# RAM_FLASH.net
KiCad netlist of a schematic drawn in Altium Designer
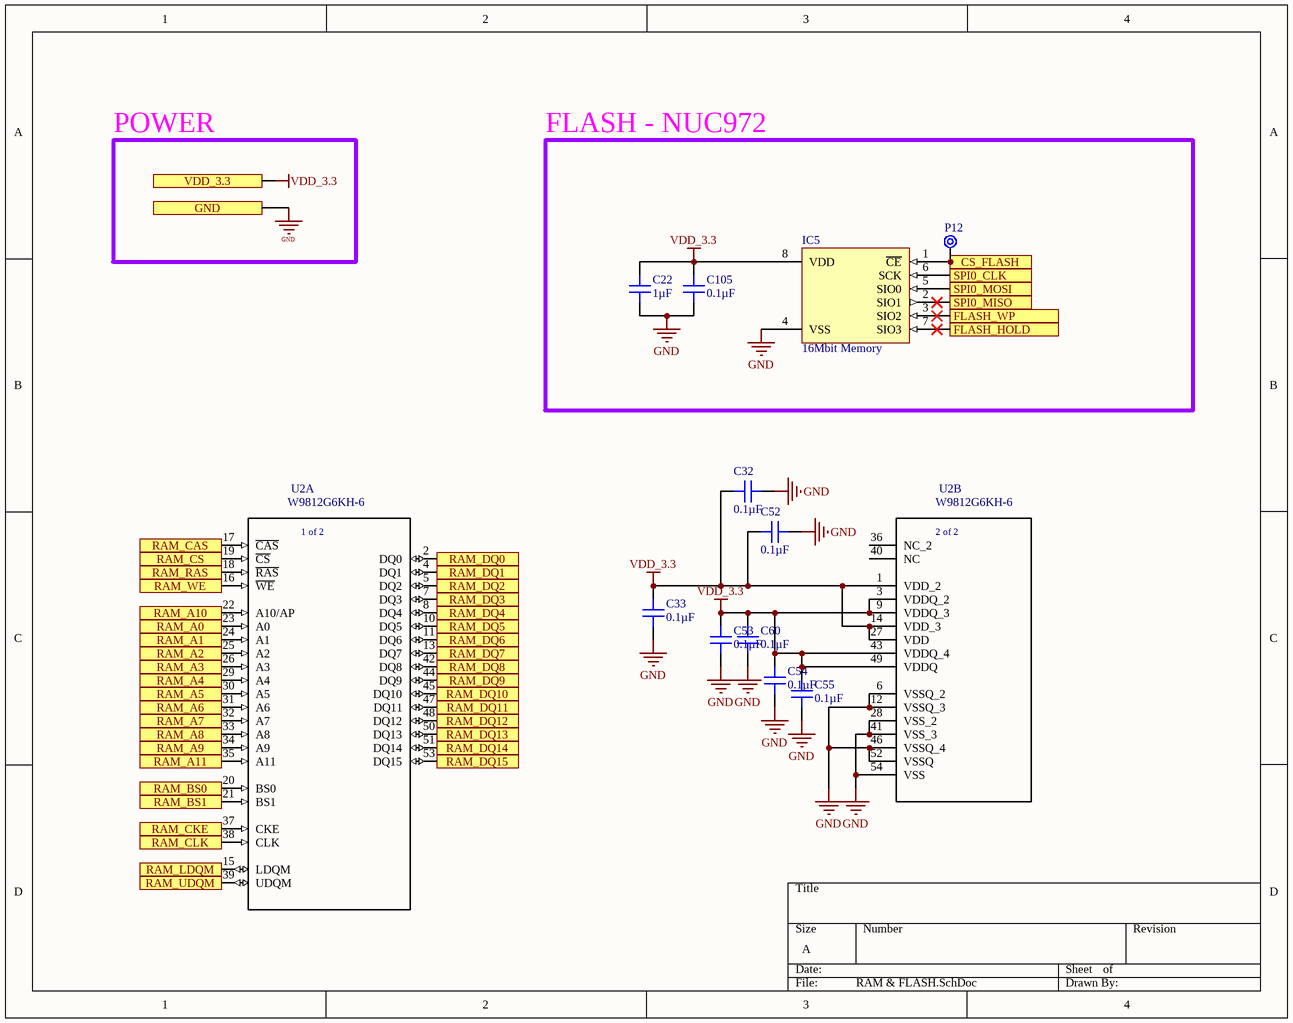
[diagram p0: RAM & FLASH.SchDoc]

(export (version "E")
  (design (tool "Eeschema 10.0.6"))
  (components
    (comp (ref "C22")
      (value "1µF")
      (footprint "CAP 0603_1608")
      (description "CAP CER 1UF 10V X7R 0603")
      (fields (field (name "MANUFACTURER") "KEMET") (field (name "VOLTAGE") "10V"))
      (libsource (lib "MVVVMAltiumDatabase") (part "Capacitor"))
    )
    (comp (ref "C32")
      (value "0.1µF")
      (footprint "CAP 0603_1608 RF")
      (description "CAP CER 0.1UF 16V X7R 0603")
      (fields (field (name "MANUFACTURER") "KEMET") (field (name "VOLTAGE") "16V"))
      (libsource (lib "MVVVMAltiumDatabase") (part "Capacitor"))
    )
    (comp (ref "C33")
      (value "0.1µF")
      (footprint "CAP 0603_1608 RF")
      (description "CAP CER 0.1UF 16V X7R 0603")
      (fields (field (name "MANUFACTURER") "KEMET") (field (name "VOLTAGE") "16V"))
      (libsource (lib "MVVVMAltiumDatabase") (part "Capacitor"))
    )
    (comp (ref "C52")
      (value "0.1µF")
      (footprint "CAP 0603_1608 RF")
      (description "CAP CER 0.1UF 16V X7R 0603")
      (fields (field (name "MANUFACTURER") "KEMET") (field (name "VOLTAGE") "16V"))
      (libsource (lib "MVVVMAltiumDatabase") (part "Capacitor"))
    )
    (comp (ref "C53")
      (value "0.1µF")
      (footprint "CAP 0603_1608 RF")
      (description "CAP CER 0.1UF 16V X7R 0603")
      (fields (field (name "MANUFACTURER") "KEMET") (field (name "VOLTAGE") "16V"))
      (libsource (lib "MVVVMAltiumDatabase") (part "Capacitor"))
    )
    (comp (ref "C54")
      (value "0.1µF")
      (footprint "CAP 0603_1608 RF")
      (description "CAP CER 0.1UF 16V X7R 0603")
      (fields (field (name "MANUFACTURER") "KEMET") (field (name "VOLTAGE") "16V"))
      (libsource (lib "MVVVMAltiumDatabase") (part "Capacitor"))
    )
    (comp (ref "C55")
      (value "0.1µF")
      (footprint "CAP 0603_1608 RF")
      (description "CAP CER 0.1UF 16V X7R 0603")
      (fields (field (name "MANUFACTURER") "KEMET") (field (name "VOLTAGE") "16V"))
      (libsource (lib "MVVVMAltiumDatabase") (part "Capacitor"))
    )
    (comp (ref "C60")
      (value "0.1µF")
      (footprint "CAP 0603_1608 RF")
      (description "CAP CER 0.1UF 16V X7R 0603")
      (fields (field (name "MANUFACTURER") "KEMET") (field (name "VOLTAGE") "16V"))
      (libsource (lib "MVVVMAltiumDatabase") (part "Capacitor"))
    )
    (comp (ref "C105")
      (value "0.1µF")
      (footprint "CAP 0603_1608 RF")
      (description "CAP CER 0.1UF 16V X7R 0603")
      (fields (field (name "MANUFACTURER") "KEMET") (field (name "VOLTAGE") "16V"))
      (libsource (lib "MVVVMAltiumDatabase") (part "Capacitor"))
    )
    (comp (ref "IC5")
      (value "16Mbit Memory")
      (footprint "MICROCHIP SOIC-8 150mil Wide")
      (description "IC FLASH 4MBIT SPI 40MHZ 8SOIC")
      (fields (field (name "MANUFACTURER") "Microchip Technology"))
      (libsource (lib "MVVVMAltiumDatabase") (part "MICROCHIP FLASH SPI QUAD 8PIN"))
    )
    (comp (ref "P12")
      (value "1 Pin")
      (footprint "1PINTHRU")
      (libsource (lib "MVVVMAltiumDatabase") (part "1 PIN THRU"))
    )
    (comp (ref "U2")
      (value "W9812G6KH-6")
      (footprint "*WIN_TSOP-54_WIN")
      (description "SDRAM Memory IC 128Mb (8M x 16) Parallel 166 MHz 5 ns 54-TSOP II")
      (fields (field (name "MF") "Winbond Electronics"))
      (libsource (lib "W9812G6KH-6") (part "W9812G6KH-6"))
    )
  )
  (nets
    (net (code "1") (name "/CS_FLASH") (class "Default")
      (node (ref "IC5") (pin "1") (pinfunction "~{CE}_1") (pintype "input"))
      (node (ref "P12") (pin "1") (pinfunction "PAD_1") (pintype "passive"))
    )
    (net (code "2") (name "/FLASH_HOLD") (class "Default")
      (node (ref "IC5") (pin "7") (pinfunction "SIO3_7") (pintype "input"))
    )
    (net (code "3") (name "/FLASH_WP") (class "Default")
      (node (ref "IC5") (pin "3") (pinfunction "SIO2_3") (pintype "input"))
    )
    (net (code "4") (name "/RAM_A0") (class "Default")
      (node (ref "U2") (pin "23") (pinfunction "A0_23") (pintype "input"))
    )
    (net (code "5") (name "/RAM_A1") (class "Default")
      (node (ref "U2") (pin "24") (pinfunction "A1_24") (pintype "input"))
    )
    (net (code "6") (name "/RAM_A2") (class "Default")
      (node (ref "U2") (pin "25") (pinfunction "A2_25") (pintype "input"))
    )
    (net (code "7") (name "/RAM_A3") (class "Default")
      (node (ref "U2") (pin "26") (pinfunction "A3_26") (pintype "input"))
    )
    (net (code "8") (name "/RAM_A4") (class "Default")
      (node (ref "U2") (pin "29") (pinfunction "A4_29") (pintype "input"))
    )
    (net (code "9") (name "/RAM_A5") (class "Default")
      (node (ref "U2") (pin "30") (pinfunction "A5_30") (pintype "input"))
    )
    (net (code "10") (name "/RAM_A6") (class "Default")
      (node (ref "U2") (pin "31") (pinfunction "A6_31") (pintype "input"))
    )
    (net (code "11") (name "/RAM_A7") (class "Default")
      (node (ref "U2") (pin "32") (pinfunction "A7_32") (pintype "input"))
    )
    (net (code "12") (name "/RAM_A8") (class "Default")
      (node (ref "U2") (pin "33") (pinfunction "A8_33") (pintype "input"))
    )
    (net (code "13") (name "/RAM_A9") (class "Default")
      (node (ref "U2") (pin "34") (pinfunction "A9_34") (pintype "input"))
    )
    (net (code "14") (name "/RAM_A10") (class "Default")
      (node (ref "U2") (pin "22") (pinfunction "A10/AP_22") (pintype "input"))
    )
    (net (code "15") (name "/RAM_A11") (class "Default")
      (node (ref "U2") (pin "35") (pinfunction "A11_35") (pintype "input"))
    )
    (net (code "16") (name "/RAM_BS0") (class "Default")
      (node (ref "U2") (pin "20") (pinfunction "BS0_20") (pintype "input"))
    )
    (net (code "17") (name "/RAM_BS1") (class "Default")
      (node (ref "U2") (pin "21") (pinfunction "BS1_21") (pintype "input"))
    )
    (net (code "18") (name "/RAM_CAS") (class "Default")
      (node (ref "U2") (pin "17") (pinfunction "~{CAS}_17") (pintype "input"))
    )
    (net (code "19") (name "/RAM_CKE") (class "Default")
      (node (ref "U2") (pin "37") (pinfunction "CKE_37") (pintype "input"))
    )
    (net (code "20") (name "/RAM_CLK") (class "Default")
      (node (ref "U2") (pin "38") (pinfunction "CLK_38") (pintype "input"))
    )
    (net (code "21") (name "/RAM_CS") (class "Default")
      (node (ref "U2") (pin "19") (pinfunction "~{CS}_19") (pintype "input"))
    )
    (net (code "22") (name "/RAM_DQ0") (class "Default")
      (node (ref "U2") (pin "2") (pinfunction "DQ0_2") (pintype "bidirectional"))
    )
    (net (code "23") (name "/RAM_DQ1") (class "Default")
      (node (ref "U2") (pin "4") (pinfunction "DQ1_4") (pintype "bidirectional"))
    )
    (net (code "24") (name "/RAM_DQ2") (class "Default")
      (node (ref "U2") (pin "5") (pinfunction "DQ2_5") (pintype "bidirectional"))
    )
    (net (code "25") (name "/RAM_DQ3") (class "Default")
      (node (ref "U2") (pin "7") (pinfunction "DQ3_7") (pintype "bidirectional"))
    )
    (net (code "26") (name "/RAM_DQ4") (class "Default")
      (node (ref "U2") (pin "8") (pinfunction "DQ4_8") (pintype "bidirectional"))
    )
    (net (code "27") (name "/RAM_DQ5") (class "Default")
      (node (ref "U2") (pin "10") (pinfunction "DQ5_10") (pintype "bidirectional"))
    )
    (net (code "28") (name "/RAM_DQ6") (class "Default")
      (node (ref "U2") (pin "11") (pinfunction "DQ6_11") (pintype "bidirectional"))
    )
    (net (code "29") (name "/RAM_DQ7") (class "Default")
      (node (ref "U2") (pin "13") (pinfunction "DQ7_13") (pintype "bidirectional"))
    )
    (net (code "30") (name "/RAM_DQ8") (class "Default")
      (node (ref "U2") (pin "42") (pinfunction "DQ8_42") (pintype "bidirectional"))
    )
    (net (code "31") (name "/RAM_DQ9") (class "Default")
      (node (ref "U2") (pin "44") (pinfunction "DQ9_44") (pintype "bidirectional"))
    )
    (net (code "32") (name "/RAM_DQ10") (class "Default")
      (node (ref "U2") (pin "45") (pinfunction "DQ10_45") (pintype "bidirectional"))
    )
    (net (code "33") (name "/RAM_DQ11") (class "Default")
      (node (ref "U2") (pin "47") (pinfunction "DQ11_47") (pintype "bidirectional"))
    )
    (net (code "34") (name "/RAM_DQ12") (class "Default")
      (node (ref "U2") (pin "48") (pinfunction "DQ12_48") (pintype "bidirectional"))
    )
    (net (code "35") (name "/RAM_DQ13") (class "Default")
      (node (ref "U2") (pin "50") (pinfunction "DQ13_50") (pintype "bidirectional"))
    )
    (net (code "36") (name "/RAM_DQ14") (class "Default")
      (node (ref "U2") (pin "51") (pinfunction "DQ14_51") (pintype "bidirectional"))
    )
    (net (code "37") (name "/RAM_DQ15") (class "Default")
      (node (ref "U2") (pin "53") (pinfunction "DQ15_53") (pintype "bidirectional"))
    )
    (net (code "38") (name "/RAM_LDQM") (class "Default")
      (node (ref "U2") (pin "15") (pinfunction "LDQM_15") (pintype "bidirectional"))
    )
    (net (code "39") (name "/RAM_RAS") (class "Default")
      (node (ref "U2") (pin "18") (pinfunction "~{RAS}_18") (pintype "input"))
    )
    (net (code "40") (name "/RAM_UDQM") (class "Default")
      (node (ref "U2") (pin "39") (pinfunction "UDQM_39") (pintype "bidirectional"))
    )
    (net (code "41") (name "/RAM_WE") (class "Default")
      (node (ref "U2") (pin "16") (pinfunction "~{WE}_16") (pintype "input"))
    )
    (net (code "42") (name "/SPI0_CLK") (class "Default")
      (node (ref "IC5") (pin "6") (pinfunction "SCK_6") (pintype "input"))
    )
    (net (code "43") (name "/SPI0_MISO") (class "Default")
      (node (ref "IC5") (pin "2") (pinfunction "SIO1_2") (pintype "output"))
    )
    (net (code "44") (name "/SPI0_MOSI") (class "Default")
      (node (ref "IC5") (pin "5") (pinfunction "SIO0_5") (pintype "input"))
    )
    (net (code "45") (name "GND") (class "Default")
      (node (ref "C105") (pin "2") (pinfunction "2_2") (pintype "passive"))
      (node (ref "C22") (pin "1") (pinfunction "1_1") (pintype "passive"))
      (node (ref "C32") (pin "2") (pinfunction "2_2") (pintype "passive"))
      (node (ref "C33") (pin "2") (pinfunction "2_2") (pintype "passive"))
      (node (ref "C52") (pin "2") (pinfunction "2_2") (pintype "passive"))
      (node (ref "C53") (pin "2") (pinfunction "2_2") (pintype "passive"))
      (node (ref "C54") (pin "2") (pinfunction "2_2") (pintype "passive"))
      (node (ref "C55") (pin "2") (pinfunction "2_2") (pintype "passive"))
      (node (ref "C60") (pin "2") (pinfunction "2_2") (pintype "passive"))
      (node (ref "IC5") (pin "4") (pinfunction "VSS_4") (pintype "passive"))
      (node (ref "U2") (pin "12") (pinfunction "VSSQ_3_12") (pintype "power_in"))
      (node (ref "U2") (pin "28") (pinfunction "VSS_2_28") (pintype "power_in"))
      (node (ref "U2") (pin "41") (pinfunction "VSS_3_41") (pintype "power_in"))
      (node (ref "U2") (pin "46") (pinfunction "VSSQ_4_46") (pintype "power_in"))
      (node (ref "U2") (pin "52") (pinfunction "VSSQ_52") (pintype "power_in"))
      (node (ref "U2") (pin "54") (pinfunction "VSS_54") (pintype "power_in"))
      (node (ref "U2") (pin "6") (pinfunction "VSSQ_2_6") (pintype "power_in"))
    )
    (net (code "46") (name "VDD_3.3") (class "Default")
      (node (ref "C105") (pin "1") (pinfunction "1_1") (pintype "passive"))
      (node (ref "C22") (pin "2") (pinfunction "2_2") (pintype "passive"))
      (node (ref "C32") (pin "1") (pinfunction "1_1") (pintype "passive"))
      (node (ref "C33") (pin "1") (pinfunction "1_1") (pintype "passive"))
      (node (ref "C52") (pin "1") (pinfunction "1_1") (pintype "passive"))
      (node (ref "C53") (pin "1") (pinfunction "1_1") (pintype "passive"))
      (node (ref "C54") (pin "1") (pinfunction "1_1") (pintype "passive"))
      (node (ref "C55") (pin "1") (pinfunction "1_1") (pintype "passive"))
      (node (ref "C60") (pin "1") (pinfunction "1_1") (pintype "passive"))
      (node (ref "IC5") (pin "8") (pinfunction "VDD_8") (pintype "passive"))
      (node (ref "U2") (pin "1") (pinfunction "VDD_2_1") (pintype "power_in"))
      (node (ref "U2") (pin "14") (pinfunction "VDD_3_14") (pintype "power_in"))
      (node (ref "U2") (pin "27") (pinfunction "VDD_27") (pintype "power_in"))
      (node (ref "U2") (pin "3") (pinfunction "VDDQ_2_3") (pintype "power_in"))
      (node (ref "U2") (pin "43") (pinfunction "VDDQ_4_43") (pintype "power_in"))
      (node (ref "U2") (pin "49") (pinfunction "VDDQ_49") (pintype "power_in"))
      (node (ref "U2") (pin "9") (pinfunction "VDDQ_3_9") (pintype "power_in"))
    )
    (net (code "47") (name "unconnected-(U2B-NC-Pad40)") (class "Default")
      (node (ref "U2") (pin "40") (pinfunction "NC_40") (pintype "passive"))
    )
    (net (code "48") (name "unconnected-(U2B-NC_2-Pad36)") (class "Default")
      (node (ref "U2") (pin "36") (pinfunction "NC_2_36") (pintype "passive"))
    )
  )
)
